# CPU_PHY.net
KiCad netlist of a schematic drawn in Altium Designer
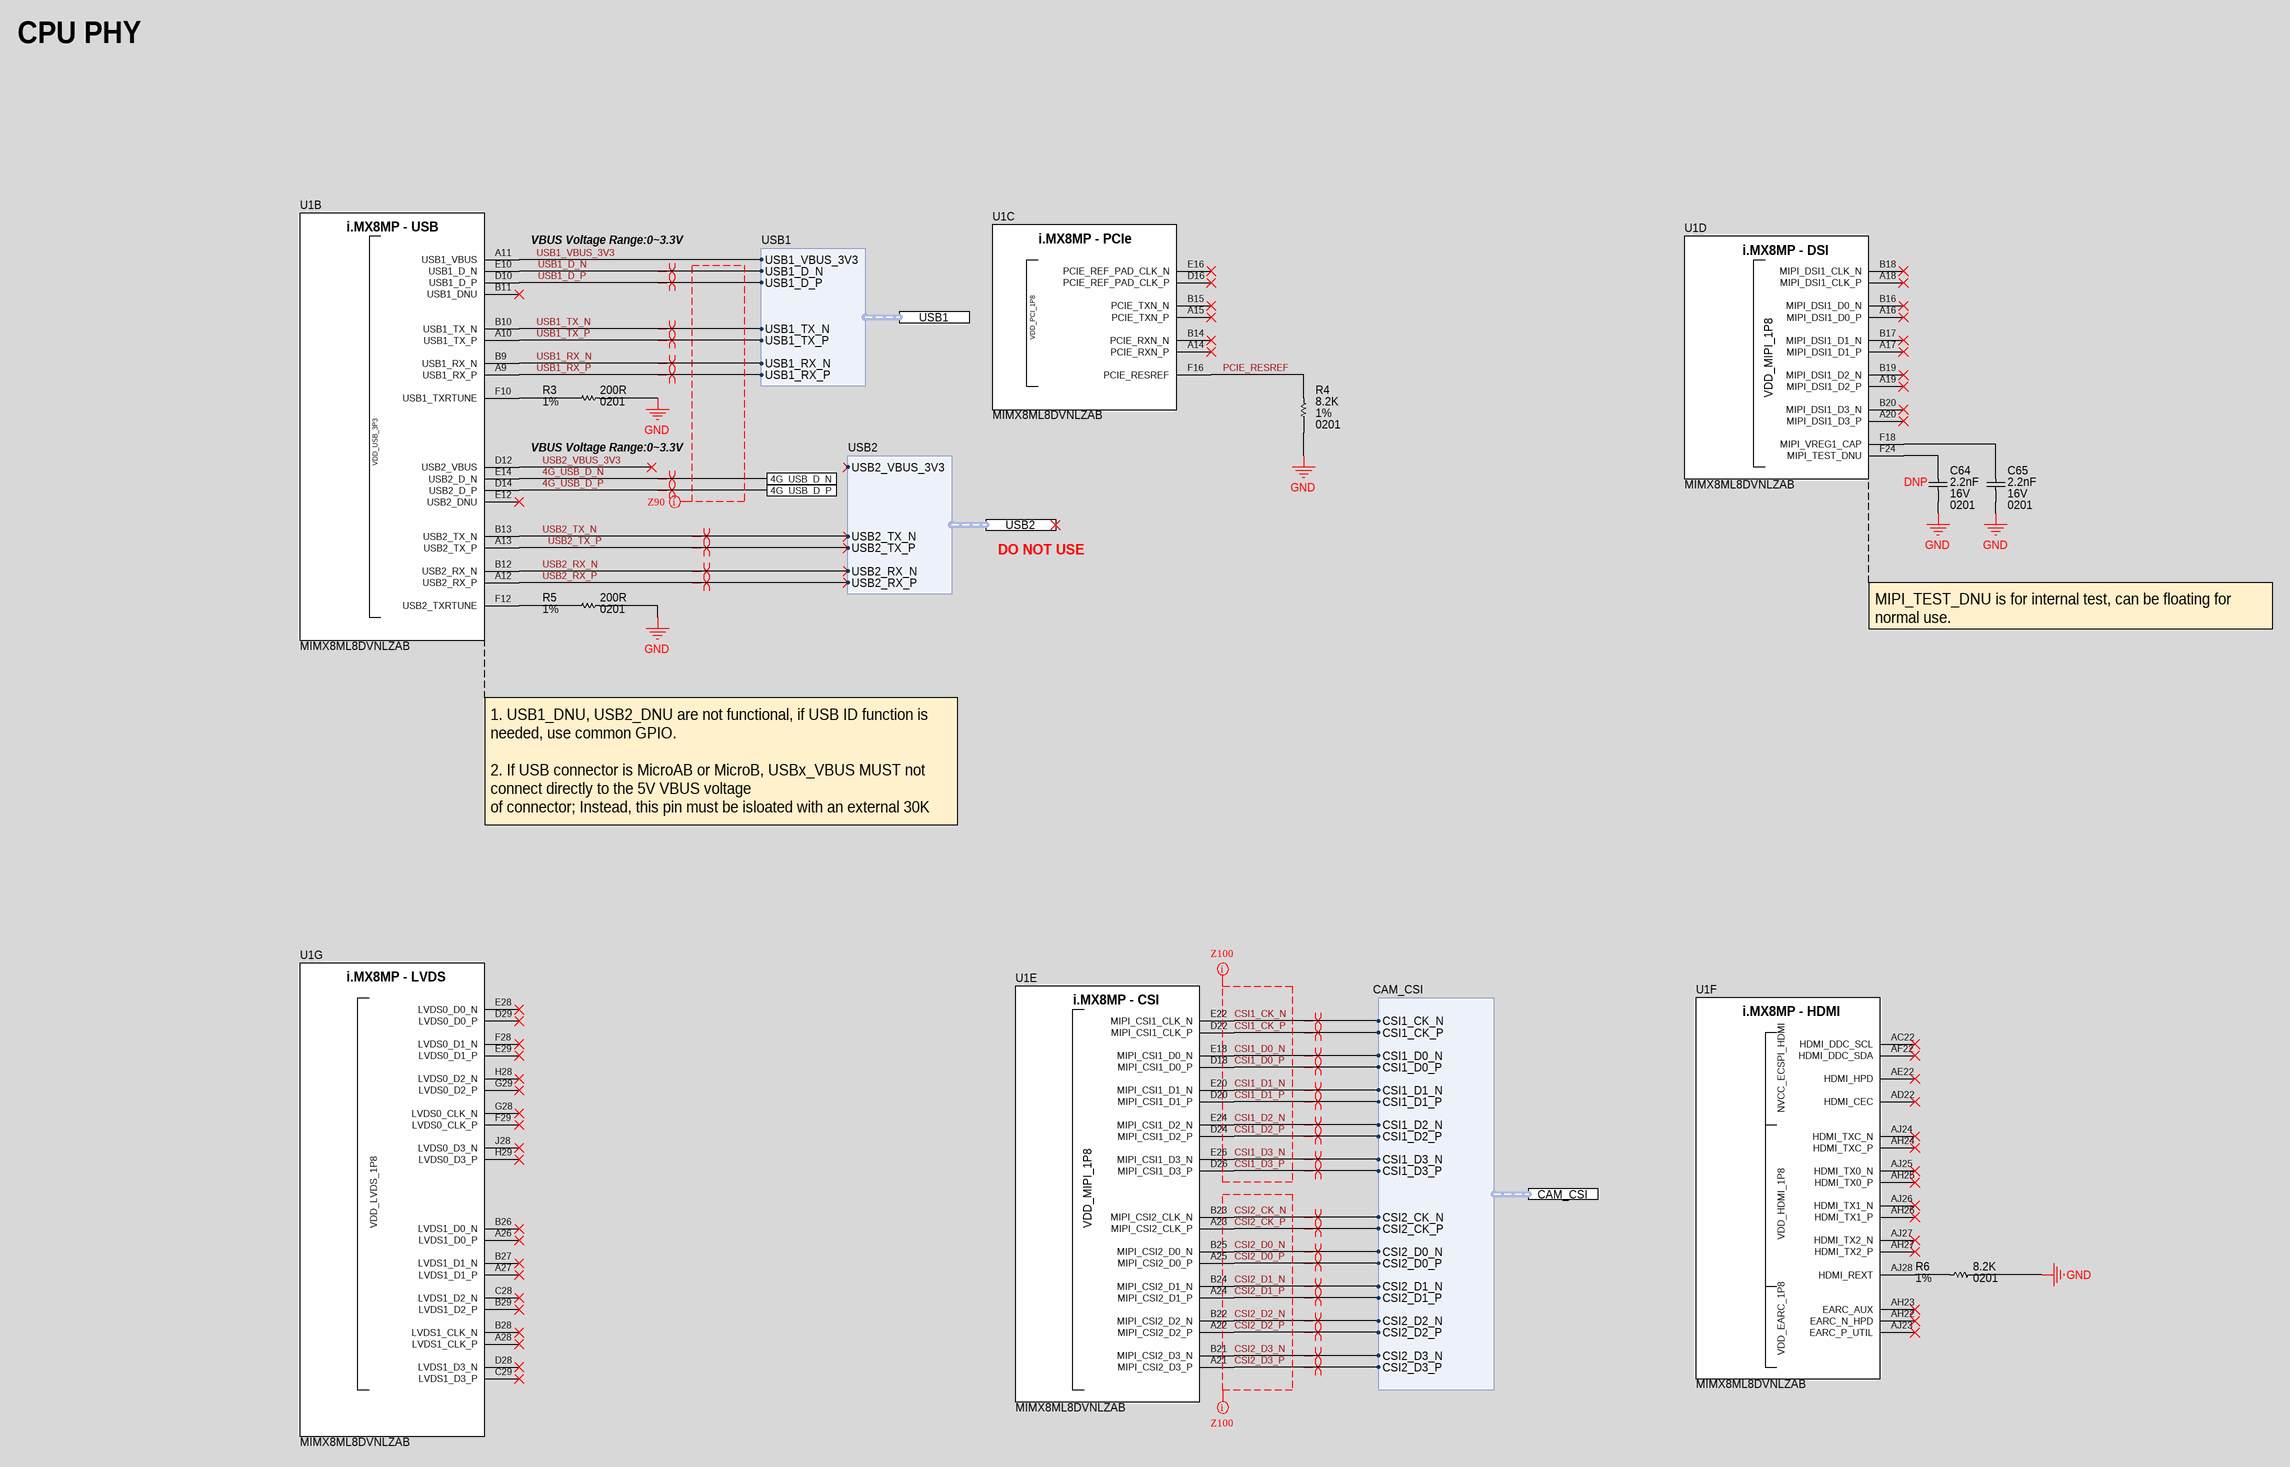
[diagram p0: CPU PHY.SchDoc]

(export (version "E")
  (design (tool "Eeschema 10.0.6"))
  (components
    (comp (ref "C64")
      (value "GRM033R71C222KA88D")
      (footprint "CAP_0201_CAPC0603X03N")
      (description "Multilayer Ceramic Capacitor, 2200 pF, 16 V, ± 10%, X7R, 0201 [0603 Metric]")
      (fields
        (field (name "MANUFACTURER") "Murata")
        (field (name "TOLERANCE") "10%")
        (field (name "VOLTAGE RATING") "16V")
        (field (name "CAPACITANCE") "2.2nF")
        (field (name "CASE/PACKAGE") "0201")
      )
      (libsource (lib "Electronic Devices_LIB") (part "CAP_2200pF_16V_X7R_0201"))
    )
    (comp (ref "C65")
      (value "GRM033R71C222KA88D")
      (footprint "CAP_0201_CAPC0603X03N")
      (description "Multilayer Ceramic Capacitor, 2200 pF, 16 V, ± 10%, X7R, 0201 [0603 Metric]")
      (fields
        (field (name "MANUFACTURER") "Murata")
        (field (name "TOLERANCE") "10%")
        (field (name "VOLTAGE RATING") "16V")
        (field (name "CAPACITANCE") "2.2nF")
        (field (name "CASE/PACKAGE") "0201")
      )
      (libsource (lib "Electronic Devices_LIB") (part "CAP_2200pF_16V_X7R_0201"))
    )
    (comp (ref "R3")
      (value "RC0201FR-07200RL")
      (footprint "RES_0201_RESC0603X02N")
      (description "SMD Chip Resistor, 200 Ohm, ± 1%, 50 mW, 0201 [0603 Metric], Thick Film, General Purpose")
      (fields
        (field (name "MANUFACTURER") "Yageo")
        (field (name "TOLERANCE") "1%")
        (field (name "RESISTANCE") "200R")
        (field (name "CASE/PACKAGE") "0201")
      )
      (libsource (lib "Electronic Devices_LIB") (part "RES_200R_1%_50mW_0201"))
    )
    (comp (ref "R4")
      (value "RC0201FR-078K2L")
      (footprint "RES_0201_RESC0603X02N")
      (description "Res Thick Film 0201 8.2K Ohm 1% 1/20W ±200ppm/°C Molded SMD Paper T/R")
      (fields
        (field (name "MANUFACTURER") "Yageo")
        (field (name "TOLERANCE") "1%")
        (field (name "RESISTANCE") "8.2K")
        (field (name "CASE/PACKAGE") "0201")
      )
      (libsource (lib "Electronic Devices_LIB") (part "RES_8.2K_1%_50mW_0201"))
    )
    (comp (ref "R5")
      (value "RC0201FR-07200RL")
      (footprint "RES_0201_RESC0603X02N")
      (description "SMD Chip Resistor, 200 Ohm, ± 1%, 50 mW, 0201 [0603 Metric], Thick Film, General Purpose")
      (fields
        (field (name "MANUFACTURER") "Yageo")
        (field (name "TOLERANCE") "1%")
        (field (name "RESISTANCE") "200R")
        (field (name "CASE/PACKAGE") "0201")
      )
      (libsource (lib "Electronic Devices_LIB") (part "RES_200R_1%_50mW_0201"))
    )
    (comp (ref "R6")
      (value "RC0201FR-078K2L")
      (footprint "RES_0201_RESC0603X02N")
      (description "Res Thick Film 0201 8.2K Ohm 1% 1/20W ±200ppm/°C Molded SMD Paper T/R")
      (fields
        (field (name "MANUFACTURER") "Yageo")
        (field (name "TOLERANCE") "1%")
        (field (name "RESISTANCE") "8.2K")
        (field (name "CASE/PACKAGE") "0201")
      )
      (libsource (lib "Electronic Devices_LIB") (part "RES_8.2K_1%_50mW_0201"))
    )
    (comp (ref "U1")
      (value "MIMX8ML8DVNLZAB")
      (footprint "IC_MPU_BGA548C50P29X29_1500X1500X148")
      (description "i.MX 8M Plus, Consumer, / TRAY TRAY MULTIPLE DP BAKEABLE RoHS Compliant: Yes")
      (fields (field (name "MANUFACTURER") "NXP Semiconductors"))
      (libsource (lib "Electronic Devices_LIB") (part "IC_MPU_8M_PLUS_MIMX8ML8DVNLZAB"))
    )
  )
  (nets
    (net (code "4") (name "/4G_USB_D_N") (class "Default")
      (node (ref "U1") (pin "E14") (pinfunction "USB2_D_N_E14") (pintype "passive"))
    )
    (net (code "5") (name "/4G_USB_D_P") (class "Default")
      (node (ref "U1") (pin "D14") (pinfunction "USB2_D_P_D14") (pintype "passive"))
    )
    (net (code "6") (name "/CSI1_CK_N") (class "Default")
      (node (ref "U1") (pin "E22") (pinfunction "MIPI_CSI1_CLK_N_E22") (pintype "passive"))
    )
    (net (code "7") (name "/CSI1_CK_P") (class "Default")
      (node (ref "U1") (pin "D22") (pinfunction "MIPI_CSI1_CLK_P_D22") (pintype "passive"))
    )
    (net (code "8") (name "/CSI1_D0_N") (class "Default")
      (node (ref "U1") (pin "E18") (pinfunction "MIPI_CSI1_D0_N_E18") (pintype "passive"))
    )
    (net (code "9") (name "/CSI1_D0_P") (class "Default")
      (node (ref "U1") (pin "D18") (pinfunction "MIPI_CSI1_D0_P_D18") (pintype "passive"))
    )
    (net (code "10") (name "/CSI1_D1_N") (class "Default")
      (node (ref "U1") (pin "E20") (pinfunction "MIPI_CSI1_D1_N_E20") (pintype "passive"))
    )
    (net (code "11") (name "/CSI1_D1_P") (class "Default")
      (node (ref "U1") (pin "D20") (pinfunction "MIPI_CSI1_D1_P_D20") (pintype "passive"))
    )
    (net (code "12") (name "/CSI1_D2_N") (class "Default")
      (node (ref "U1") (pin "E24") (pinfunction "MIPI_CSI1_D2_N_E24") (pintype "passive"))
    )
    (net (code "13") (name "/CSI1_D2_P") (class "Default")
      (node (ref "U1") (pin "D24") (pinfunction "MIPI_CSI1_D2_P_D24") (pintype "passive"))
    )
    (net (code "14") (name "/CSI1_D3_N") (class "Default")
      (node (ref "U1") (pin "E26") (pinfunction "MIPI_CSI1_D3_N_E26") (pintype "passive"))
    )
    (net (code "15") (name "/CSI1_D3_P") (class "Default")
      (node (ref "U1") (pin "D26") (pinfunction "MIPI_CSI1_D3_P_D26") (pintype "passive"))
    )
    (net (code "16") (name "/CSI2_CK_N") (class "Default")
      (node (ref "U1") (pin "B23") (pinfunction "MIPI_CSI2_CLK_N_B23") (pintype "passive"))
    )
    (net (code "17") (name "/CSI2_CK_P") (class "Default")
      (node (ref "U1") (pin "A23") (pinfunction "MIPI_CSI2_CLK_P_A23") (pintype "passive"))
    )
    (net (code "18") (name "/CSI2_D0_N") (class "Default")
      (node (ref "U1") (pin "B25") (pinfunction "MIPI_CSI2_D0_N_B25") (pintype "passive"))
    )
    (net (code "19") (name "/CSI2_D0_P") (class "Default")
      (node (ref "U1") (pin "A25") (pinfunction "MIPI_CSI2_D0_P_A25") (pintype "passive"))
    )
    (net (code "20") (name "/CSI2_D1_N") (class "Default")
      (node (ref "U1") (pin "B24") (pinfunction "MIPI_CSI2_D1_N_B24") (pintype "passive"))
    )
    (net (code "21") (name "/CSI2_D1_P") (class "Default")
      (node (ref "U1") (pin "A24") (pinfunction "MIPI_CSI2_D1_P_A24") (pintype "passive"))
    )
    (net (code "22") (name "/CSI2_D2_N") (class "Default")
      (node (ref "U1") (pin "B22") (pinfunction "MIPI_CSI2_D2_N_B22") (pintype "passive"))
    )
    (net (code "23") (name "/CSI2_D2_P") (class "Default")
      (node (ref "U1") (pin "A22") (pinfunction "MIPI_CSI2_D2_P_A22") (pintype "passive"))
    )
    (net (code "24") (name "/CSI2_D3_N") (class "Default")
      (node (ref "U1") (pin "B21") (pinfunction "MIPI_CSI2_D3_N_B21") (pintype "passive"))
    )
    (net (code "25") (name "/CSI2_D3_P") (class "Default")
      (node (ref "U1") (pin "A21") (pinfunction "MIPI_CSI2_D3_P_A21") (pintype "passive"))
    )
    (net (code "26") (name "/PCIE_RESREF") (class "Default")
      (node (ref "R4") (pin "2") (pinfunction "2_2") (pintype "passive"))
      (node (ref "U1") (pin "F16") (pinfunction "PCIE_RESREF_F16") (pintype "passive"))
    )
    (net (code "27") (name "/USB1_D_N") (class "Default")
      (node (ref "U1") (pin "E10") (pinfunction "USB1_D_N_E10") (pintype "passive"))
    )
    (net (code "28") (name "/USB1_D_P") (class "Default")
      (node (ref "U1") (pin "D10") (pinfunction "USB1_D_P_D10") (pintype "passive"))
    )
    (net (code "29") (name "/USB1_RX_N") (class "Default")
      (node (ref "U1") (pin "B9") (pinfunction "USB1_RX_N_B9") (pintype "passive"))
    )
    (net (code "30") (name "/USB1_RX_P") (class "Default")
      (node (ref "U1") (pin "A9") (pinfunction "USB1_RX_P_A9") (pintype "passive"))
    )
    (net (code "31") (name "/USB1_TX_N") (class "Default")
      (node (ref "U1") (pin "B10") (pinfunction "USB1_TX_N_B10") (pintype "passive"))
    )
    (net (code "32") (name "/USB1_TX_P") (class "Default")
      (node (ref "U1") (pin "A10") (pinfunction "USB1_TX_P_A10") (pintype "passive"))
    )
    (net (code "33") (name "/USB1_VBUS_3V3") (class "Default")
      (node (ref "U1") (pin "A11") (pinfunction "USB1_VBUS_A11") (pintype "passive"))
    )
    (net (code "34") (name "/USB2_RX_N") (class "Default")
      (node (ref "U1") (pin "B12") (pinfunction "USB2_RX_N_B12") (pintype "passive+no_connect"))
    )
    (net (code "35") (name "/USB2_RX_P") (class "Default")
      (node (ref "U1") (pin "A12") (pinfunction "USB2_RX_P_A12") (pintype "passive+no_connect"))
    )
    (net (code "36") (name "/USB2_TX_N") (class "Default")
      (node (ref "U1") (pin "B13") (pinfunction "USB2_TX_N_B13") (pintype "passive+no_connect"))
    )
    (net (code "37") (name "/USB2_TX_P") (class "Default")
      (node (ref "U1") (pin "A13") (pinfunction "USB2_TX_P_A13") (pintype "passive+no_connect"))
    )
    (net (code "38") (name "/USB2_VBUS_3V3") (class "Default")
      (node (ref "U1") (pin "D12") (pinfunction "USB2_VBUS_D12") (pintype "passive+no_connect"))
    )
    (net (code "42") (name "GND") (class "Default")
      (node (ref "C64") (pin "1") (pinfunction "1_1") (pintype "passive"))
      (node (ref "C65") (pin "1") (pinfunction "1_1") (pintype "passive"))
      (node (ref "R3") (pin "2") (pinfunction "2_2") (pintype "passive"))
      (node (ref "R4") (pin "1") (pinfunction "1_1") (pintype "passive"))
      (node (ref "R5") (pin "2") (pinfunction "2_2") (pintype "passive"))
      (node (ref "R6") (pin "1") (pinfunction "1_1") (pintype "passive"))
    )
    (net (code "43") (name "Net-(U1B-USB1_TXRTUNE)") (class "Default")
      (node (ref "R3") (pin "1") (pinfunction "1_1") (pintype "passive"))
      (node (ref "U1") (pin "F10") (pinfunction "USB1_TXRTUNE_F10") (pintype "passive"))
    )
    (net (code "44") (name "Net-(U1B-USB2_TXRTUNE)") (class "Default")
      (node (ref "R5") (pin "1") (pinfunction "1_1") (pintype "passive"))
      (node (ref "U1") (pin "F12") (pinfunction "USB2_TXRTUNE_F12") (pintype "passive"))
    )
    (net (code "45") (name "Net-(U1D-MIPI_TEST_DNU)") (class "Default")
      (node (ref "C64") (pin "2") (pinfunction "2_2") (pintype "passive"))
      (node (ref "U1") (pin "F24") (pinfunction "MIPI_TEST_DNU_F24") (pintype "passive"))
    )
    (net (code "46") (name "Net-(U1D-MIPI_VREG1_CAP)") (class "Default")
      (node (ref "C65") (pin "2") (pinfunction "2_2") (pintype "passive"))
      (node (ref "U1") (pin "F18") (pinfunction "MIPI_VREG1_CAP_F18") (pintype "passive"))
    )
    (net (code "47") (name "Net-(U1F-HDMI_REXT)") (class "Default")
      (node (ref "R6") (pin "2") (pinfunction "2_2") (pintype "passive"))
      (node (ref "U1") (pin "AJ28") (pinfunction "HDMI_REXT_AJ28") (pintype "passive"))
    )
    (net (code "48") (name "unconnected-(U1B-USB1_DNU-PadB11)") (class "Default")
      (node (ref "U1") (pin "B11") (pinfunction "USB1_DNU_B11") (pintype "passive+no_connect"))
    )
    (net (code "49") (name "unconnected-(U1B-USB2_DNU-PadE12)") (class "Default")
      (node (ref "U1") (pin "E12") (pinfunction "USB2_DNU_E12") (pintype "passive+no_connect"))
    )
    (net (code "50") (name "unconnected-(U1C-PCIE_REF_PAD_CLK_N-PadE16)") (class "Default")
      (node (ref "U1") (pin "E16") (pinfunction "PCIE_REF_PAD_CLK_N_E16") (pintype "passive+no_connect"))
    )
    (net (code "51") (name "unconnected-(U1C-PCIE_REF_PAD_CLK_P-PadD16)") (class "Default")
      (node (ref "U1") (pin "D16") (pinfunction "PCIE_REF_PAD_CLK_P_D16") (pintype "passive+no_connect"))
    )
    (net (code "52") (name "unconnected-(U1C-PCIE_RXN_N-PadB14)") (class "Default")
      (node (ref "U1") (pin "B14") (pinfunction "PCIE_RXN_N_B14") (pintype "passive+no_connect"))
    )
    (net (code "53") (name "unconnected-(U1C-PCIE_RXN_P-PadA14)") (class "Default")
      (node (ref "U1") (pin "A14") (pinfunction "PCIE_RXN_P_A14") (pintype "passive+no_connect"))
    )
    (net (code "54") (name "unconnected-(U1C-PCIE_TXN_N-PadB15)") (class "Default")
      (node (ref "U1") (pin "B15") (pinfunction "PCIE_TXN_N_B15") (pintype "passive+no_connect"))
    )
    (net (code "55") (name "unconnected-(U1C-PCIE_TXN_P-PadA15)") (class "Default")
      (node (ref "U1") (pin "A15") (pinfunction "PCIE_TXN_P_A15") (pintype "passive+no_connect"))
    )
    (net (code "56") (name "unconnected-(U1D-MIPI_DSI1_CLK_N-PadB18)") (class "Default")
      (node (ref "U1") (pin "B18") (pinfunction "MIPI_DSI1_CLK_N_B18") (pintype "passive+no_connect"))
    )
    (net (code "57") (name "unconnected-(U1D-MIPI_DSI1_CLK_P-PadA18)") (class "Default")
      (node (ref "U1") (pin "A18") (pinfunction "MIPI_DSI1_CLK_P_A18") (pintype "passive+no_connect"))
    )
    (net (code "58") (name "unconnected-(U1D-MIPI_DSI1_D0_N-PadB16)") (class "Default")
      (node (ref "U1") (pin "B16") (pinfunction "MIPI_DSI1_D0_N_B16") (pintype "passive+no_connect"))
    )
    (net (code "59") (name "unconnected-(U1D-MIPI_DSI1_D0_P-PadA16)") (class "Default")
      (node (ref "U1") (pin "A16") (pinfunction "MIPI_DSI1_D0_P_A16") (pintype "passive+no_connect"))
    )
    (net (code "60") (name "unconnected-(U1D-MIPI_DSI1_D1_N-PadB17)") (class "Default")
      (node (ref "U1") (pin "B17") (pinfunction "MIPI_DSI1_D1_N_B17") (pintype "passive+no_connect"))
    )
    (net (code "61") (name "unconnected-(U1D-MIPI_DSI1_D1_P-PadA17)") (class "Default")
      (node (ref "U1") (pin "A17") (pinfunction "MIPI_DSI1_D1_P_A17") (pintype "passive+no_connect"))
    )
    (net (code "62") (name "unconnected-(U1D-MIPI_DSI1_D2_N-PadB19)") (class "Default")
      (node (ref "U1") (pin "B19") (pinfunction "MIPI_DSI1_D2_N_B19") (pintype "passive+no_connect"))
    )
    (net (code "63") (name "unconnected-(U1D-MIPI_DSI1_D2_P-PadA19)") (class "Default")
      (node (ref "U1") (pin "A19") (pinfunction "MIPI_DSI1_D2_P_A19") (pintype "passive+no_connect"))
    )
    (net (code "64") (name "unconnected-(U1D-MIPI_DSI1_D3_N-PadB20)") (class "Default")
      (node (ref "U1") (pin "B20") (pinfunction "MIPI_DSI1_D3_N_B20") (pintype "passive+no_connect"))
    )
    (net (code "65") (name "unconnected-(U1D-MIPI_DSI1_D3_P-PadA20)") (class "Default")
      (node (ref "U1") (pin "A20") (pinfunction "MIPI_DSI1_D3_P_A20") (pintype "passive+no_connect"))
    )
    (net (code "66") (name "unconnected-(U1F-EARC_AUX-PadAH23)") (class "Default")
      (node (ref "U1") (pin "AH23") (pinfunction "EARC_AUX_AH23") (pintype "passive+no_connect"))
    )
    (net (code "67") (name "unconnected-(U1F-EARC_N_HPD-PadAH22)") (class "Default")
      (node (ref "U1") (pin "AH22") (pinfunction "EARC_N_HPD_AH22") (pintype "passive+no_connect"))
    )
    (net (code "68") (name "unconnected-(U1F-EARC_P_UTIL-PadAJ23)") (class "Default")
      (node (ref "U1") (pin "AJ23") (pinfunction "EARC_P_UTIL_AJ23") (pintype "passive+no_connect"))
    )
    (net (code "69") (name "unconnected-(U1F-HDMI_CEC-PadAD22)") (class "Default")
      (node (ref "U1") (pin "AD22") (pinfunction "HDMI_CEC_AD22") (pintype "passive+no_connect"))
    )
    (net (code "70") (name "unconnected-(U1F-HDMI_DDC_SCL-PadAC22)") (class "Default")
      (node (ref "U1") (pin "AC22") (pinfunction "HDMI_DDC_SCL_AC22") (pintype "passive+no_connect"))
    )
    (net (code "71") (name "unconnected-(U1F-HDMI_DDC_SDA-PadAF22)") (class "Default")
      (node (ref "U1") (pin "AF22") (pinfunction "HDMI_DDC_SDA_AF22") (pintype "passive+no_connect"))
    )
    (net (code "72") (name "unconnected-(U1F-HDMI_HPD-PadAE22)") (class "Default")
      (node (ref "U1") (pin "AE22") (pinfunction "HDMI_HPD_AE22") (pintype "passive+no_connect"))
    )
    (net (code "73") (name "unconnected-(U1F-HDMI_TX0_N-PadAJ25)") (class "Default")
      (node (ref "U1") (pin "AJ25") (pinfunction "HDMI_TX0_N_AJ25") (pintype "passive+no_connect"))
    )
    (net (code "74") (name "unconnected-(U1F-HDMI_TX0_P-PadAH25)") (class "Default")
      (node (ref "U1") (pin "AH25") (pinfunction "HDMI_TX0_P_AH25") (pintype "passive+no_connect"))
    )
    (net (code "75") (name "unconnected-(U1F-HDMI_TX1_N-PadAJ26)") (class "Default")
      (node (ref "U1") (pin "AJ26") (pinfunction "HDMI_TX1_N_AJ26") (pintype "passive+no_connect"))
    )
    (net (code "76") (name "unconnected-(U1F-HDMI_TX1_P-PadAH26)") (class "Default")
      (node (ref "U1") (pin "AH26") (pinfunction "HDMI_TX1_P_AH26") (pintype "passive+no_connect"))
    )
    (net (code "77") (name "unconnected-(U1F-HDMI_TX2_N-PadAJ27)") (class "Default")
      (node (ref "U1") (pin "AJ27") (pinfunction "HDMI_TX2_N_AJ27") (pintype "passive+no_connect"))
    )
    (net (code "78") (name "unconnected-(U1F-HDMI_TX2_P-PadAH27)") (class "Default")
      (node (ref "U1") (pin "AH27") (pinfunction "HDMI_TX2_P_AH27") (pintype "passive+no_connect"))
    )
    (net (code "79") (name "unconnected-(U1F-HDMI_TXC_N-PadAJ24)") (class "Default")
      (node (ref "U1") (pin "AJ24") (pinfunction "HDMI_TXC_N_AJ24") (pintype "passive+no_connect"))
    )
    (net (code "80") (name "unconnected-(U1F-HDMI_TXC_P-PadAH24)") (class "Default")
      (node (ref "U1") (pin "AH24") (pinfunction "HDMI_TXC_P_AH24") (pintype "passive+no_connect"))
    )
    (net (code "81") (name "unconnected-(U1G-LVDS0_CLK_N-PadG28)") (class "Default")
      (node (ref "U1") (pin "G28") (pinfunction "LVDS0_CLK_N_G28") (pintype "passive+no_connect"))
    )
    (net (code "82") (name "unconnected-(U1G-LVDS0_CLK_P-PadF29)") (class "Default")
      (node (ref "U1") (pin "F29") (pinfunction "LVDS0_CLK_P_F29") (pintype "passive+no_connect"))
    )
    (net (code "83") (name "unconnected-(U1G-LVDS0_D0_N-PadE28)") (class "Default")
      (node (ref "U1") (pin "E28") (pinfunction "LVDS0_D0_N_E28") (pintype "passive+no_connect"))
    )
    (net (code "84") (name "unconnected-(U1G-LVDS0_D0_P-PadD29)") (class "Default")
      (node (ref "U1") (pin "D29") (pinfunction "LVDS0_D0_P_D29") (pintype "passive+no_connect"))
    )
    (net (code "85") (name "unconnected-(U1G-LVDS0_D1_N-PadF28)") (class "Default")
      (node (ref "U1") (pin "F28") (pinfunction "LVDS0_D1_N_F28") (pintype "passive+no_connect"))
    )
    (net (code "86") (name "unconnected-(U1G-LVDS0_D1_P-PadE29)") (class "Default")
      (node (ref "U1") (pin "E29") (pinfunction "LVDS0_D1_P_E29") (pintype "passive+no_connect"))
    )
    (net (code "87") (name "unconnected-(U1G-LVDS0_D2_N-PadH28)") (class "Default")
      (node (ref "U1") (pin "H28") (pinfunction "LVDS0_D2_N_H28") (pintype "passive+no_connect"))
    )
    (net (code "88") (name "unconnected-(U1G-LVDS0_D2_P-PadG29)") (class "Default")
      (node (ref "U1") (pin "G29") (pinfunction "LVDS0_D2_P_G29") (pintype "passive+no_connect"))
    )
    (net (code "89") (name "unconnected-(U1G-LVDS0_D3_N-PadJ28)") (class "Default")
      (node (ref "U1") (pin "J28") (pinfunction "LVDS0_D3_N_J28") (pintype "passive+no_connect"))
    )
    (net (code "90") (name "unconnected-(U1G-LVDS0_D3_P-PadH29)") (class "Default")
      (node (ref "U1") (pin "H29") (pinfunction "LVDS0_D3_P_H29") (pintype "passive+no_connect"))
    )
    (net (code "91") (name "unconnected-(U1G-LVDS1_CLK_N-PadB28)") (class "Default")
      (node (ref "U1") (pin "B28") (pinfunction "LVDS1_CLK_N_B28") (pintype "passive+no_connect"))
    )
    (net (code "92") (name "unconnected-(U1G-LVDS1_CLK_P-PadA28)") (class "Default")
      (node (ref "U1") (pin "A28") (pinfunction "LVDS1_CLK_P_A28") (pintype "passive+no_connect"))
    )
    (net (code "93") (name "unconnected-(U1G-LVDS1_D0_N-PadB26)") (class "Default")
      (node (ref "U1") (pin "B26") (pinfunction "LVDS1_D0_N_B26") (pintype "passive+no_connect"))
    )
    (net (code "94") (name "unconnected-(U1G-LVDS1_D0_P-PadA26)") (class "Default")
      (node (ref "U1") (pin "A26") (pinfunction "LVDS1_D0_P_A26") (pintype "passive+no_connect"))
    )
    (net (code "95") (name "unconnected-(U1G-LVDS1_D1_N-PadB27)") (class "Default")
      (node (ref "U1") (pin "B27") (pinfunction "LVDS1_D1_N_B27") (pintype "passive+no_connect"))
    )
    (net (code "96") (name "unconnected-(U1G-LVDS1_D1_P-PadA27)") (class "Default")
      (node (ref "U1") (pin "A27") (pinfunction "LVDS1_D1_P_A27") (pintype "passive+no_connect"))
    )
    (net (code "97") (name "unconnected-(U1G-LVDS1_D2_N-PadC28)") (class "Default")
      (node (ref "U1") (pin "C28") (pinfunction "LVDS1_D2_N_C28") (pintype "passive+no_connect"))
    )
    (net (code "98") (name "unconnected-(U1G-LVDS1_D2_P-PadB29)") (class "Default")
      (node (ref "U1") (pin "B29") (pinfunction "LVDS1_D2_P_B29") (pintype "passive+no_connect"))
    )
    (net (code "99") (name "unconnected-(U1G-LVDS1_D3_N-PadD28)") (class "Default")
      (node (ref "U1") (pin "D28") (pinfunction "LVDS1_D3_N_D28") (pintype "passive+no_connect"))
    )
    (net (code "100") (name "unconnected-(U1G-LVDS1_D3_P-PadC29)") (class "Default")
      (node (ref "U1") (pin "C29") (pinfunction "LVDS1_D3_P_C29") (pintype "passive+no_connect"))
    )
  )
)
